# L3mk5ExRam.net
KiCad netlist of a schematic drawn in EAGLE
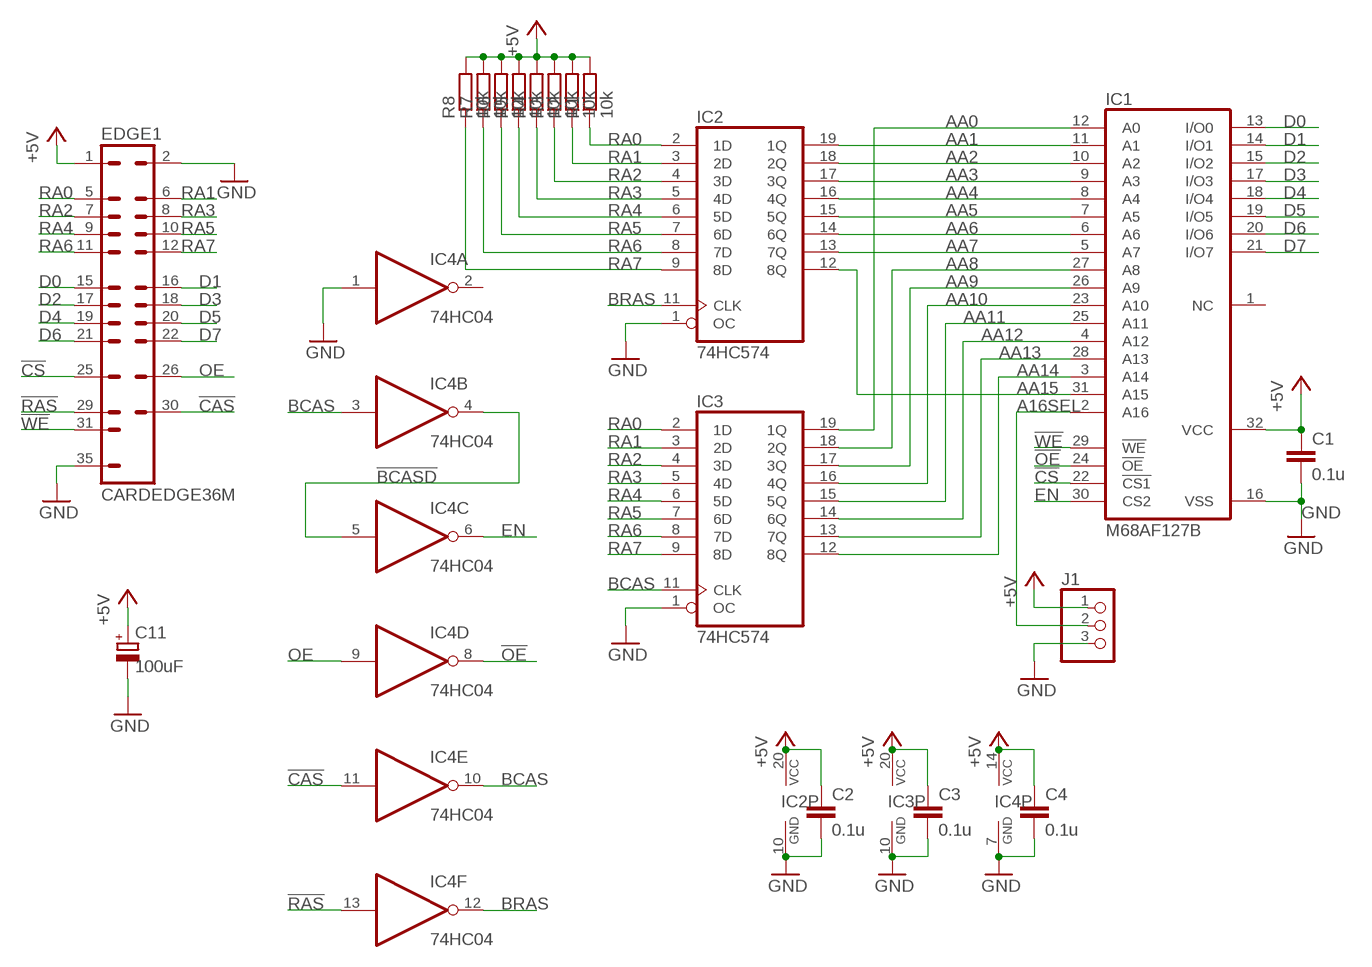
[diagram p0: schematic, sheet 1]

(export (version "E")
  (design (tool "Eeschema 10.0.6"))
  (components
    (comp (ref "C1")
      (value "0.1u")
      (footprint "eagle-import:C025-024X044")
      (libsource (lib "eagle-import") (part "C-EU025-024X044"))
    )
    (comp (ref "C2")
      (value "0.1u")
      (footprint "eagle-import:C025-024X044")
      (libsource (lib "eagle-import") (part "C-EU025-024X044"))
    )
    (comp (ref "C3")
      (value "0.1u")
      (footprint "eagle-import:C025-024X044")
      (libsource (lib "eagle-import") (part "C-EU025-024X044"))
    )
    (comp (ref "C4")
      (value "0.1u")
      (footprint "eagle-import:C025-024X044")
      (libsource (lib "eagle-import") (part "C-EU025-024X044"))
    )
    (comp (ref "C11")
      (value "100uF")
      (footprint "eagle-import:E2-5")
      (libsource (lib "eagle-import") (part "CPOL-EUE2-5"))
    )
    (comp (ref "EDGE1")
      (value "CARDEDGE36M")
      (footprint "eagle-import:PM")
      (libsource (lib "eagle-import") (part "CARDEDGE36M"))
    )
    (comp (ref "IC1")
      (value "M68AF127B")
      (footprint "eagle-import:SOJ32-400")
      (libsource (lib "eagle-import") (part "M68AF127B"))
    )
    (comp (ref "IC2")
      (value "74HC574")
      (footprint "eagle-import:DIL20")
      (libsource (lib "eagle-import") (part "74574NHC"))
    )
    (comp (ref "IC3")
      (value "74HC574")
      (footprint "eagle-import:DIL20")
      (libsource (lib "eagle-import") (part "74574NHC"))
    )
    (comp (ref "IC4")
      (value "74HC04")
      (footprint "eagle-import:DIL14")
      (libsource (lib "eagle-import") (part "7404NHC"))
    )
    (comp (ref "J1")
      (value "PINHD-1X3")
      (footprint "eagle-import:1X03")
      (libsource (lib "eagle-import") (part "PINHD-1X3"))
    )
    (comp (ref "R1")
      (value "10k")
      (footprint "eagle-import:0204V")
      (libsource (lib "eagle-import") (part "R-EU_0204/2V"))
    )
    (comp (ref "R2")
      (value "10k")
      (footprint "eagle-import:0204V")
      (libsource (lib "eagle-import") (part "R-EU_0204/2V"))
    )
    (comp (ref "R3")
      (value "10k")
      (footprint "eagle-import:0204V")
      (libsource (lib "eagle-import") (part "R-EU_0204/2V"))
    )
    (comp (ref "R4")
      (value "10k")
      (footprint "eagle-import:0204V")
      (libsource (lib "eagle-import") (part "R-EU_0204/2V"))
    )
    (comp (ref "R5")
      (value "10k")
      (footprint "eagle-import:0204V")
      (libsource (lib "eagle-import") (part "R-EU_0204/2V"))
    )
    (comp (ref "R6")
      (value "10k")
      (footprint "eagle-import:0204V")
      (libsource (lib "eagle-import") (part "R-EU_0204/2V"))
    )
    (comp (ref "R7")
      (value "10k")
      (footprint "eagle-import:0204V")
      (libsource (lib "eagle-import") (part "R-EU_0204/2V"))
    )
    (comp (ref "R8")
      (value "10k")
      (footprint "eagle-import:0204V")
      (libsource (lib "eagle-import") (part "R-EU_0204/2V"))
    )
  )
  (nets
    (net (code "1") (name "+5V") (class "Default")
      (node (ref "C1") (pin "1") (pinfunction "1_1") (pintype "passive"))
      (node (ref "C11") (pin "+") (pinfunction "+_+") (pintype "passive"))
      (node (ref "C2") (pin "1") (pinfunction "1_1") (pintype "passive"))
      (node (ref "C3") (pin "1") (pinfunction "1_1") (pintype "passive"))
      (node (ref "C4") (pin "1") (pinfunction "1_1") (pintype "passive"))
      (node (ref "EDGE1") (pin "1") (pinfunction "1_1") (pintype "passive"))
      (node (ref "IC1") (pin "32") (pinfunction "VCC_32") (pintype "power_in"))
      (node (ref "IC2") (pin "20") (pinfunction "VCC_20") (pintype "power_in"))
      (node (ref "IC3") (pin "20") (pinfunction "VCC_20") (pintype "power_in"))
      (node (ref "IC4") (pin "14") (pinfunction "VCC_14") (pintype "power_in"))
      (node (ref "J1") (pin "1") (pinfunction "1_1") (pintype "passive"))
      (node (ref "R1") (pin "2") (pinfunction "2_2") (pintype "passive"))
      (node (ref "R2") (pin "2") (pinfunction "2_2") (pintype "passive"))
      (node (ref "R3") (pin "2") (pinfunction "2_2") (pintype "passive"))
      (node (ref "R4") (pin "2") (pinfunction "2_2") (pintype "passive"))
      (node (ref "R5") (pin "2") (pinfunction "2_2") (pintype "passive"))
      (node (ref "R6") (pin "2") (pinfunction "2_2") (pintype "passive"))
      (node (ref "R7") (pin "2") (pinfunction "2_2") (pintype "passive"))
      (node (ref "R8") (pin "2") (pinfunction "2_2") (pintype "passive"))
    )
    (net (code "2") (name "/A16SEL") (class "Default")
      (node (ref "IC1") (pin "2") (pinfunction "A16_2") (pintype "input"))
      (node (ref "J1") (pin "2") (pinfunction "2_2") (pintype "passive"))
    )
    (net (code "3") (name "/AA0") (class "Default")
      (node (ref "IC1") (pin "12") (pinfunction "A0_12") (pintype "input"))
      (node (ref "IC3") (pin "19") (pinfunction "1Q_19") (pintype "tri_state"))
    )
    (net (code "4") (name "/AA1") (class "Default")
      (node (ref "IC1") (pin "11") (pinfunction "A1_11") (pintype "input"))
      (node (ref "IC2") (pin "19") (pinfunction "1Q_19") (pintype "tri_state"))
    )
    (net (code "5") (name "/AA2") (class "Default")
      (node (ref "IC1") (pin "10") (pinfunction "A2_10") (pintype "input"))
      (node (ref "IC2") (pin "18") (pinfunction "2Q_18") (pintype "tri_state"))
    )
    (net (code "6") (name "/AA3") (class "Default")
      (node (ref "IC1") (pin "9") (pinfunction "A3_9") (pintype "input"))
      (node (ref "IC2") (pin "17") (pinfunction "3Q_17") (pintype "tri_state"))
    )
    (net (code "7") (name "/AA4") (class "Default")
      (node (ref "IC1") (pin "8") (pinfunction "A4_8") (pintype "input"))
      (node (ref "IC2") (pin "16") (pinfunction "4Q_16") (pintype "tri_state"))
    )
    (net (code "8") (name "/AA5") (class "Default")
      (node (ref "IC1") (pin "7") (pinfunction "A5_7") (pintype "input"))
      (node (ref "IC2") (pin "15") (pinfunction "5Q_15") (pintype "tri_state"))
    )
    (net (code "9") (name "/AA6") (class "Default")
      (node (ref "IC1") (pin "6") (pinfunction "A6_6") (pintype "input"))
      (node (ref "IC2") (pin "14") (pinfunction "6Q_14") (pintype "tri_state"))
    )
    (net (code "10") (name "/AA7") (class "Default")
      (node (ref "IC1") (pin "5") (pinfunction "A7_5") (pintype "input"))
      (node (ref "IC2") (pin "13") (pinfunction "7Q_13") (pintype "tri_state"))
    )
    (net (code "11") (name "/AA8") (class "Default")
      (node (ref "IC1") (pin "27") (pinfunction "A8_27") (pintype "input"))
      (node (ref "IC3") (pin "18") (pinfunction "2Q_18") (pintype "tri_state"))
    )
    (net (code "12") (name "/AA9") (class "Default")
      (node (ref "IC1") (pin "26") (pinfunction "A9_26") (pintype "input"))
      (node (ref "IC3") (pin "17") (pinfunction "3Q_17") (pintype "tri_state"))
    )
    (net (code "13") (name "/AA10") (class "Default")
      (node (ref "IC1") (pin "23") (pinfunction "A10_23") (pintype "input"))
      (node (ref "IC3") (pin "16") (pinfunction "4Q_16") (pintype "tri_state"))
    )
    (net (code "14") (name "/AA11") (class "Default")
      (node (ref "IC1") (pin "25") (pinfunction "A11_25") (pintype "input"))
      (node (ref "IC3") (pin "15") (pinfunction "5Q_15") (pintype "tri_state"))
    )
    (net (code "15") (name "/AA12") (class "Default")
      (node (ref "IC1") (pin "4") (pinfunction "A12_4") (pintype "input"))
      (node (ref "IC3") (pin "14") (pinfunction "6Q_14") (pintype "tri_state"))
    )
    (net (code "16") (name "/AA13") (class "Default")
      (node (ref "IC1") (pin "28") (pinfunction "A13_28") (pintype "input"))
      (node (ref "IC3") (pin "13") (pinfunction "7Q_13") (pintype "tri_state"))
    )
    (net (code "17") (name "/AA14") (class "Default")
      (node (ref "IC1") (pin "3") (pinfunction "A14_3") (pintype "input"))
      (node (ref "IC3") (pin "12") (pinfunction "8Q_12") (pintype "tri_state"))
    )
    (net (code "18") (name "/AA15") (class "Default")
      (node (ref "IC1") (pin "31") (pinfunction "A15_31") (pintype "input"))
      (node (ref "IC2") (pin "12") (pinfunction "8Q_12") (pintype "tri_state"))
    )
    (net (code "19") (name "/BCAS") (class "Default")
      (node (ref "IC3") (pin "11") (pinfunction "CLK_11") (pintype "input"))
      (node (ref "IC4") (pin "10") (pinfunction "O_10") (pintype "output"))
      (node (ref "IC4") (pin "3") (pinfunction "I_3") (pintype "input"))
    )
    (net (code "20") (name "/BRAS") (class "Default")
      (node (ref "IC2") (pin "11") (pinfunction "CLK_11") (pintype "input"))
      (node (ref "IC4") (pin "12") (pinfunction "O_12") (pintype "output"))
    )
    (net (code "21") (name "/D0") (class "Default")
      (node (ref "EDGE1") (pin "15") (pinfunction "15_15") (pintype "passive"))
      (node (ref "IC1") (pin "13") (pinfunction "I/O0_13") (pintype "bidirectional"))
    )
    (net (code "22") (name "/D1") (class "Default")
      (node (ref "EDGE1") (pin "16") (pinfunction "16_16") (pintype "passive"))
      (node (ref "IC1") (pin "14") (pinfunction "I/O1_14") (pintype "bidirectional"))
    )
    (net (code "23") (name "/D2") (class "Default")
      (node (ref "EDGE1") (pin "17") (pinfunction "17_17") (pintype "passive"))
      (node (ref "IC1") (pin "15") (pinfunction "I/O2_15") (pintype "bidirectional"))
    )
    (net (code "24") (name "/D3") (class "Default")
      (node (ref "EDGE1") (pin "18") (pinfunction "18_18") (pintype "passive"))
      (node (ref "IC1") (pin "17") (pinfunction "I/O3_17") (pintype "bidirectional"))
    )
    (net (code "25") (name "/D4") (class "Default")
      (node (ref "EDGE1") (pin "19") (pinfunction "19_19") (pintype "passive"))
      (node (ref "IC1") (pin "18") (pinfunction "I/O4_18") (pintype "bidirectional"))
    )
    (net (code "26") (name "/D5") (class "Default")
      (node (ref "EDGE1") (pin "20") (pinfunction "20_20") (pintype "passive"))
      (node (ref "IC1") (pin "19") (pinfunction "I/O5_19") (pintype "bidirectional"))
    )
    (net (code "27") (name "/D6") (class "Default")
      (node (ref "EDGE1") (pin "21") (pinfunction "21_21") (pintype "passive"))
      (node (ref "IC1") (pin "20") (pinfunction "I/O6_20") (pintype "bidirectional"))
    )
    (net (code "28") (name "/D7") (class "Default")
      (node (ref "EDGE1") (pin "22") (pinfunction "22_22") (pintype "passive"))
      (node (ref "IC1") (pin "21") (pinfunction "I/O7_21") (pintype "bidirectional"))
    )
    (net (code "29") (name "/EN") (class "Default")
      (node (ref "IC1") (pin "30") (pinfunction "CS2_30") (pintype "input"))
      (node (ref "IC4") (pin "6") (pinfunction "O_6") (pintype "output"))
    )
    (net (code "30") (name "/OE") (class "Default")
      (node (ref "EDGE1") (pin "26") (pinfunction "26_26") (pintype "passive"))
      (node (ref "IC4") (pin "9") (pinfunction "I_9") (pintype "input"))
    )
    (net (code "31") (name "/RA0") (class "Default")
      (node (ref "EDGE1") (pin "5") (pinfunction "5_5") (pintype "passive"))
      (node (ref "IC2") (pin "2") (pinfunction "1D_2") (pintype "input"))
      (node (ref "IC3") (pin "2") (pinfunction "1D_2") (pintype "input"))
      (node (ref "R1") (pin "1") (pinfunction "1_1") (pintype "passive"))
    )
    (net (code "32") (name "/RA1") (class "Default")
      (node (ref "EDGE1") (pin "6") (pinfunction "6_6") (pintype "passive"))
      (node (ref "IC2") (pin "3") (pinfunction "2D_3") (pintype "input"))
      (node (ref "IC3") (pin "3") (pinfunction "2D_3") (pintype "input"))
      (node (ref "R2") (pin "1") (pinfunction "1_1") (pintype "passive"))
    )
    (net (code "33") (name "/RA2") (class "Default")
      (node (ref "EDGE1") (pin "7") (pinfunction "7_7") (pintype "passive"))
      (node (ref "IC2") (pin "4") (pinfunction "3D_4") (pintype "input"))
      (node (ref "IC3") (pin "4") (pinfunction "3D_4") (pintype "input"))
      (node (ref "R3") (pin "1") (pinfunction "1_1") (pintype "passive"))
    )
    (net (code "34") (name "/RA3") (class "Default")
      (node (ref "EDGE1") (pin "8") (pinfunction "8_8") (pintype "passive"))
      (node (ref "IC2") (pin "5") (pinfunction "4D_5") (pintype "input"))
      (node (ref "IC3") (pin "5") (pinfunction "4D_5") (pintype "input"))
      (node (ref "R4") (pin "1") (pinfunction "1_1") (pintype "passive"))
    )
    (net (code "35") (name "/RA4") (class "Default")
      (node (ref "EDGE1") (pin "9") (pinfunction "9_9") (pintype "passive"))
      (node (ref "IC2") (pin "6") (pinfunction "5D_6") (pintype "input"))
      (node (ref "IC3") (pin "6") (pinfunction "5D_6") (pintype "input"))
      (node (ref "R5") (pin "1") (pinfunction "1_1") (pintype "passive"))
    )
    (net (code "36") (name "/RA5") (class "Default")
      (node (ref "EDGE1") (pin "10") (pinfunction "10_10") (pintype "passive"))
      (node (ref "IC2") (pin "7") (pinfunction "6D_7") (pintype "input"))
      (node (ref "IC3") (pin "7") (pinfunction "6D_7") (pintype "input"))
      (node (ref "R6") (pin "1") (pinfunction "1_1") (pintype "passive"))
    )
    (net (code "37") (name "/RA6") (class "Default")
      (node (ref "EDGE1") (pin "11") (pinfunction "11_11") (pintype "passive"))
      (node (ref "IC2") (pin "8") (pinfunction "7D_8") (pintype "input"))
      (node (ref "IC3") (pin "8") (pinfunction "7D_8") (pintype "input"))
      (node (ref "R7") (pin "1") (pinfunction "1_1") (pintype "passive"))
    )
    (net (code "38") (name "/RA7") (class "Default")
      (node (ref "EDGE1") (pin "12") (pinfunction "12_12") (pintype "passive"))
      (node (ref "IC2") (pin "9") (pinfunction "8D_9") (pintype "input"))
      (node (ref "IC3") (pin "9") (pinfunction "8D_9") (pintype "input"))
      (node (ref "R8") (pin "1") (pinfunction "1_1") (pintype "passive"))
    )
    (net (code "39") (name "/~{BCASD}") (class "Default")
      (node (ref "IC4") (pin "4") (pinfunction "O_4") (pintype "output"))
      (node (ref "IC4") (pin "5") (pinfunction "I_5") (pintype "input"))
    )
    (net (code "40") (name "/~{CAS}") (class "Default")
      (node (ref "EDGE1") (pin "30") (pinfunction "30_30") (pintype "passive"))
      (node (ref "IC4") (pin "11") (pinfunction "I_11") (pintype "input"))
    )
    (net (code "41") (name "/~{CS}") (class "Default")
      (node (ref "EDGE1") (pin "25") (pinfunction "25_25") (pintype "passive"))
      (node (ref "IC1") (pin "22") (pinfunction "~{CS1}_22") (pintype "input"))
    )
    (net (code "42") (name "/~{OE}") (class "Default")
      (node (ref "IC1") (pin "24") (pinfunction "~{OE}_24") (pintype "input"))
      (node (ref "IC4") (pin "8") (pinfunction "O_8") (pintype "output"))
    )
    (net (code "43") (name "/~{RAS}") (class "Default")
      (node (ref "EDGE1") (pin "29") (pinfunction "29_29") (pintype "passive"))
      (node (ref "IC4") (pin "13") (pinfunction "I_13") (pintype "input"))
    )
    (net (code "44") (name "/~{WE}") (class "Default")
      (node (ref "EDGE1") (pin "31") (pinfunction "31_31") (pintype "passive"))
      (node (ref "IC1") (pin "29") (pinfunction "~{WE}_29") (pintype "input"))
    )
    (net (code "45") (name "GND") (class "Default")
      (node (ref "C1") (pin "2") (pinfunction "2_2") (pintype "passive"))
      (node (ref "C11") (pin "-") (pinfunction "-_-") (pintype "passive"))
      (node (ref "C2") (pin "2") (pinfunction "2_2") (pintype "passive"))
      (node (ref "C3") (pin "2") (pinfunction "2_2") (pintype "passive"))
      (node (ref "C4") (pin "2") (pinfunction "2_2") (pintype "passive"))
      (node (ref "EDGE1") (pin "2") (pinfunction "2_2") (pintype "passive"))
      (node (ref "EDGE1") (pin "35") (pinfunction "35_35") (pintype "passive"))
      (node (ref "IC1") (pin "16") (pinfunction "VSS_16") (pintype "power_in"))
      (node (ref "IC2") (pin "1") (pinfunction "OC_1") (pintype "input"))
      (node (ref "IC2") (pin "10") (pinfunction "GND_10") (pintype "power_in"))
      (node (ref "IC3") (pin "1") (pinfunction "OC_1") (pintype "input"))
      (node (ref "IC3") (pin "10") (pinfunction "GND_10") (pintype "power_in"))
      (node (ref "IC4") (pin "1") (pinfunction "I_1") (pintype "input"))
      (node (ref "IC4") (pin "7") (pinfunction "GND_7") (pintype "power_in"))
      (node (ref "J1") (pin "3") (pinfunction "3_3") (pintype "passive"))
    )
    (net (code "46") (name "unconnected-(IC1-NC-Pad1)") (class "Default")
      (node (ref "IC1") (pin "1") (pinfunction "NC_1") (pintype "no_connect"))
    )
    (net (code "47") (name "unconnected-(IC4A-O-Pad2)") (class "Default")
      (node (ref "IC4") (pin "2") (pinfunction "O_2") (pintype "output"))
    )
  )
)
